# Energetski_dio.net
KiCad netlist of a schematic drawn in Altium Designer
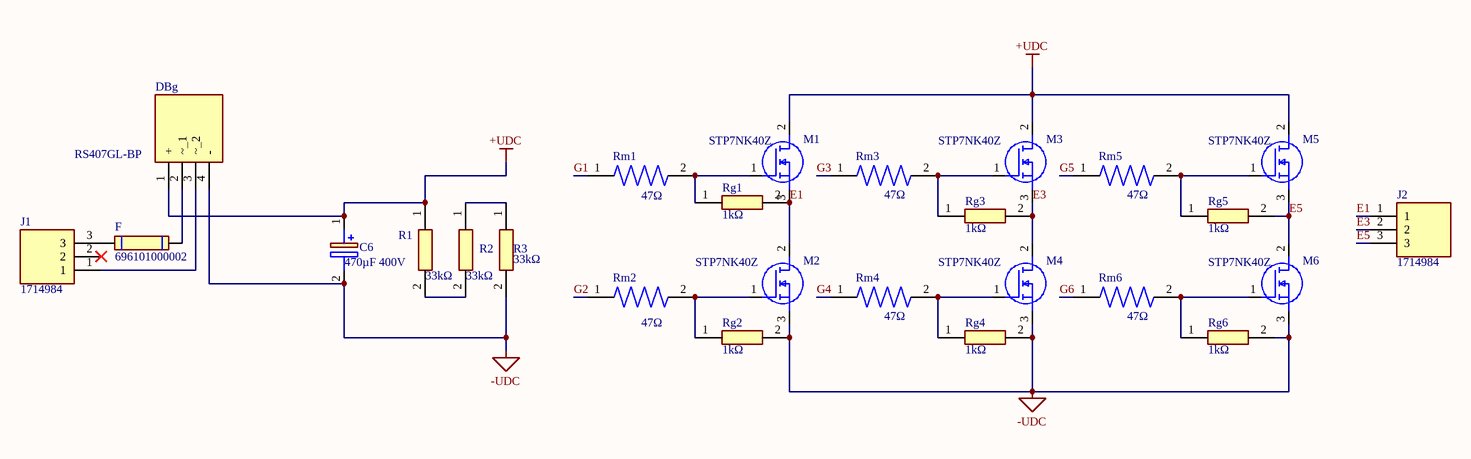
[diagram p0: Energetski_dio.SchDoc]

(export (version "E")
  (design (tool "Eeschema 10.0.6"))
  (components
    (comp (ref "C6")
      (value "470µF 400V")
      (footprint "6")
      (description "Capacitor Polarised")
      (fields
        (field (name "MANUFACTURER_PART_NUMBER") "LLG2G471MELB35")
        (field (name "MOUSER PART NUMBER") "647-LLG2G471MELB35")
      )
      (libsource (lib "Trofazni_invertor_SchLib") (part "LLG2G471MELB35_1"))
    )
    (comp (ref "DBg")
      (value "RS407GL-BP")
      (footprint "10")
      (description "Bridge Rectifier")
      (fields (field (name "MOUSER PART NUMBER") "833-RS407GL-BP"))
      (libsource (lib "Trofazni_invertor_SchLib") (part "RS407GL-BP"))
    )
    (comp (ref "F")
      (value "696101000002")
      (footprint "696101000002")
      (description "Fuse Block 10 A 250V 1 Circuit Cartridge Through Hole")
      (fields (field (name "MF") "Wurth Elektronik"))
      (libsource (lib "Trofazni_invertor_SchLib") (part "696101000002"))
    )
    (comp (ref "J1")
      (value "1714984")
      (footprint "3")
      (description "Connector")
      (fields (field (name "MOUSER PART NUMBER") "651-1714984"))
      (libsource (lib "") (part "1714984_1"))
    )
    (comp (ref "J2")
      (value "1714984")
      (footprint "3")
      (description "Connector")
      (fields (field (name "MOUSER PART NUMBER") "651-1714984"))
      (libsource (lib "Trofazni_invertor_SchLib") (part "1714984"))
    )
    (comp (ref "M1")
      (value "STP7NK40Z")
      (footprint "2")
      (description "MOSFET (N-Channel)")
      (fields
        (field (name "MANUFACTURER_PART_NUMBER") "STP7NK40ZFP")
        (field (name "MOUSER PART NUMBER") "511-STP7NK40ZFP")
      )
      (libsource (lib "Trofazni_invertor_SchLib") (part "STP7NK40ZFP"))
    )
    (comp (ref "M2")
      (value "STP7NK40Z")
      (footprint "2")
      (description "MOSFET (N-Channel)")
      (fields
        (field (name "MANUFACTURER_PART_NUMBER") "STP7NK40ZFP")
        (field (name "MOUSER PART NUMBER") "511-STP7NK40ZFP")
      )
      (libsource (lib "Trofazni_invertor_SchLib") (part "STP7NK40ZFP"))
    )
    (comp (ref "M3")
      (value "STP7NK40Z")
      (footprint "2")
      (description "MOSFET (N-Channel)")
      (fields
        (field (name "MANUFACTURER_PART_NUMBER") "STP7NK40ZFP")
        (field (name "MOUSER PART NUMBER") "511-STP7NK40ZFP")
      )
      (libsource (lib "Trofazni_invertor_SchLib") (part "STP7NK40ZFP"))
    )
    (comp (ref "M4")
      (value "STP7NK40Z")
      (footprint "2")
      (description "MOSFET (N-Channel)")
      (fields
        (field (name "MANUFACTURER_PART_NUMBER") "STP7NK40ZFP")
        (field (name "MOUSER PART NUMBER") "511-STP7NK40ZFP")
      )
      (libsource (lib "Trofazni_invertor_SchLib") (part "STP7NK40ZFP"))
    )
    (comp (ref "M5")
      (value "STP7NK40Z")
      (footprint "2")
      (description "MOSFET (N-Channel)")
      (fields
        (field (name "MANUFACTURER_PART_NUMBER") "STP7NK40ZFP")
        (field (name "MOUSER PART NUMBER") "511-STP7NK40ZFP")
      )
      (libsource (lib "Trofazni_invertor_SchLib") (part "STP7NK40ZFP"))
    )
    (comp (ref "M6")
      (value "STP7NK40Z")
      (footprint "2")
      (description "MOSFET (N-Channel)")
      (fields
        (field (name "MANUFACTURER_PART_NUMBER") "STP7NK40ZFP")
        (field (name "MOUSER PART NUMBER") "511-STP7NK40ZFP")
      )
      (libsource (lib "Trofazni_invertor_SchLib") (part "STP7NK40ZFP"))
    )
    (comp (ref "R1")
      (value "33kΩ")
      (footprint "18")
      (description "Resistor")
      (fields
        (field (name "MANUFACTURER_PART_NUMBER") "CFR-50JB-52-33K")
        (field (name "MOUSER PART NUMBER") "603-CFR-50JB-52-33K")
      )
      (libsource (lib "Trofazni_invertor_SchLib") (part "CFR-50JB-52-33K"))
    )
    (comp (ref "R2")
      (value "33kΩ")
      (footprint "18")
      (description "Resistor")
      (fields
        (field (name "MANUFACTURER_PART_NUMBER") "CFR-50JB-52-33K")
        (field (name "MOUSER PART NUMBER") "603-CFR-50JB-52-33K")
      )
      (libsource (lib "Trofazni_invertor_SchLib") (part "CFR-50JB-52-33K"))
    )
    (comp (ref "R3")
      (value "33kΩ")
      (footprint "18")
      (description "Resistor")
      (fields
        (field (name "MANUFACTURER_PART_NUMBER") "CFR-50JB-52-33K")
        (field (name "MOUSER PART NUMBER") "603-CFR-50JB-52-33K")
      )
      (libsource (lib "Trofazni_invertor_SchLib") (part "CFR-50JB-52-33K"))
    )
    (comp (ref "Rg1")
      (value "1kΩ")
      (footprint "SamacSys:RESAD1590W60L630D240")
      (description "Resistor")
      (fields (field (name "MANUFACTURER_PART_NUMBER") "CFR-25JB-52-1K"))
      (libsource (lib "Trofazni_invertor_SchLib") (part "CFR-25JB-52-1K"))
    )
    (comp (ref "Rg2")
      (value "1kΩ")
      (footprint "SamacSys:RESAD1590W60L630D240")
      (description "Resistor")
      (fields (field (name "MANUFACTURER_PART_NUMBER") "CFR-25JB-52-1K"))
      (libsource (lib "Trofazni_invertor_SchLib") (part "CFR-25JB-52-1K"))
    )
    (comp (ref "Rg3")
      (value "1kΩ")
      (footprint "SamacSys:RESAD1590W60L630D240")
      (description "Resistor")
      (fields (field (name "MANUFACTURER_PART_NUMBER") "CFR-25JB-52-1K"))
      (libsource (lib "Trofazni_invertor_SchLib") (part "CFR-25JB-52-1K"))
    )
    (comp (ref "Rg4")
      (value "1kΩ")
      (footprint "SamacSys:RESAD1590W60L630D240")
      (description "Resistor")
      (fields (field (name "MANUFACTURER_PART_NUMBER") "CFR-25JB-52-1K"))
      (libsource (lib "Trofazni_invertor_SchLib") (part "CFR-25JB-52-1K"))
    )
    (comp (ref "Rg5")
      (value "1kΩ")
      (footprint "SamacSys:RESAD1590W60L630D240")
      (description "Resistor")
      (fields (field (name "MANUFACTURER_PART_NUMBER") "CFR-25JB-52-1K"))
      (libsource (lib "Trofazni_invertor_SchLib") (part "CFR-25JB-52-1K"))
    )
    (comp (ref "Rg6")
      (value "1kΩ")
      (footprint "SamacSys:RESAD1590W60L630D240")
      (description "Resistor")
      (fields (field (name "MANUFACTURER_PART_NUMBER") "CFR-25JB-52-1K"))
      (libsource (lib "Trofazni_invertor_SchLib") (part "CFR-25JB-52-1K"))
    )
    (comp (ref "Rm1")
      (value "47Ω")
      (footprint "17")
      (description "470 Ohms Â±5% 0.25W, 1/4W Through Hole Resistor Axial - Carbon Film")
      (fields (field (name "TOLERANCE") "5%") (field (name "MF") "TE Connectivity"))
      (libsource (lib "Trofazni_invertor_SchLib") (part "2-1623928-5"))
    )
    (comp (ref "Rm2")
      (value "47Ω")
      (footprint "17")
      (description "470 Ohms Â±5% 0.25W, 1/4W Through Hole Resistor Axial - Carbon Film")
      (fields (field (name "TOLERANCE") "5%") (field (name "MF") "TE Connectivity"))
      (libsource (lib "Trofazni_invertor_SchLib") (part "2-1623928-5"))
    )
    (comp (ref "Rm3")
      (value "47Ω")
      (footprint "17")
      (description "470 Ohms Â±5% 0.25W, 1/4W Through Hole Resistor Axial - Carbon Film")
      (fields (field (name "TOLERANCE") "5%") (field (name "MF") "TE Connectivity"))
      (libsource (lib "Trofazni_invertor_SchLib") (part "2-1623928-5"))
    )
    (comp (ref "Rm4")
      (value "47Ω")
      (footprint "17")
      (description "470 Ohms Â±5% 0.25W, 1/4W Through Hole Resistor Axial - Carbon Film")
      (fields (field (name "TOLERANCE") "5%") (field (name "MF") "TE Connectivity"))
      (libsource (lib "Trofazni_invertor_SchLib") (part "2-1623928-5"))
    )
    (comp (ref "Rm5")
      (value "47Ω")
      (footprint "17")
      (description "470 Ohms Â±5% 0.25W, 1/4W Through Hole Resistor Axial - Carbon Film")
      (fields (field (name "TOLERANCE") "5%") (field (name "MF") "TE Connectivity"))
      (libsource (lib "Trofazni_invertor_SchLib") (part "2-1623928-5"))
    )
    (comp (ref "Rm6")
      (value "47Ω")
      (footprint "17")
      (description "470 Ohms Â±5% 0.25W, 1/4W Through Hole Resistor Axial - Carbon Film")
      (fields (field (name "TOLERANCE") "5%") (field (name "MF") "TE Connectivity"))
      (libsource (lib "Trofazni_invertor_SchLib") (part "2-1623928-5"))
    )
  )
  (nets
    (net (code "1") (name "+UDC") (class "Default")
      (node (ref "C6") (pin "1") (pinfunction "+_1") (pintype "passive"))
      (node (ref "DBg") (pin "1") (pinfunction "+_1") (pintype "passive"))
      (node (ref "M1") (pin "2") (pinfunction "D_2") (pintype "passive"))
      (node (ref "M3") (pin "2") (pinfunction "D_2") (pintype "passive"))
      (node (ref "M5") (pin "2") (pinfunction "D_2") (pintype "passive"))
      (node (ref "R1") (pin "1") (pinfunction "1_1") (pintype "passive"))
    )
    (net (code "2") (name "-UDC") (class "Default")
      (node (ref "C6") (pin "2") (pinfunction "-_2") (pintype "passive"))
      (node (ref "DBg") (pin "4") (pinfunction "-_4") (pintype "passive"))
      (node (ref "M2") (pin "3") (pinfunction "S_3") (pintype "passive"))
      (node (ref "M4") (pin "3") (pinfunction "S_3") (pintype "passive"))
      (node (ref "M6") (pin "3") (pinfunction "S_3") (pintype "passive"))
      (node (ref "R3") (pin "2") (pinfunction "2_2") (pintype "passive"))
      (node (ref "Rg2") (pin "2") (pinfunction "2_2") (pintype "passive"))
      (node (ref "Rg4") (pin "2") (pinfunction "2_2") (pintype "passive"))
      (node (ref "Rg6") (pin "2") (pinfunction "2_2") (pintype "passive"))
    )
    (net (code "3") (name "/E1") (class "Default")
      (node (ref "J2") (pin "1") (pinfunction "1_1") (pintype "passive"))
      (node (ref "M1") (pin "3") (pinfunction "S_3") (pintype "passive"))
      (node (ref "M2") (pin "2") (pinfunction "D_2") (pintype "passive"))
      (node (ref "Rg1") (pin "2") (pinfunction "2_2") (pintype "passive"))
    )
    (net (code "4") (name "/E3") (class "Default")
      (node (ref "J2") (pin "2") (pinfunction "2_2") (pintype "passive"))
      (node (ref "M3") (pin "3") (pinfunction "S_3") (pintype "passive"))
      (node (ref "M4") (pin "2") (pinfunction "D_2") (pintype "passive"))
      (node (ref "Rg3") (pin "2") (pinfunction "2_2") (pintype "passive"))
    )
    (net (code "5") (name "/E5") (class "Default")
      (node (ref "J2") (pin "3") (pinfunction "3_3") (pintype "passive"))
      (node (ref "M5") (pin "3") (pinfunction "S_3") (pintype "passive"))
      (node (ref "M6") (pin "2") (pinfunction "D_2") (pintype "passive"))
      (node (ref "Rg5") (pin "2") (pinfunction "2_2") (pintype "passive"))
    )
    (net (code "6") (name "/G1") (class "Default")
      (node (ref "Rm1") (pin "1") (pinfunction "1_1") (pintype "passive"))
    )
    (net (code "7") (name "/G2") (class "Default")
      (node (ref "Rm2") (pin "1") (pinfunction "1_1") (pintype "passive"))
    )
    (net (code "8") (name "/G3") (class "Default")
      (node (ref "Rm3") (pin "1") (pinfunction "1_1") (pintype "passive"))
    )
    (net (code "9") (name "/G4") (class "Default")
      (node (ref "Rm4") (pin "1") (pinfunction "1_1") (pintype "passive"))
    )
    (net (code "10") (name "/G5") (class "Default")
      (node (ref "Rm5") (pin "1") (pinfunction "1_1") (pintype "passive"))
    )
    (net (code "11") (name "/G6") (class "Default")
      (node (ref "Rm6") (pin "1") (pinfunction "1_1") (pintype "passive"))
    )
    (net (code "12") (name "Net-(DBg-~_1)") (class "Default")
      (node (ref "DBg") (pin "2") (pinfunction "~_1_2") (pintype "passive"))
      (node (ref "F") (pin "2") (pinfunction "2_2") (pintype "passive"))
    )
    (net (code "13") (name "Net-(DBg-~_2)") (class "Default")
      (node (ref "DBg") (pin "3") (pinfunction "~_2_3") (pintype "passive"))
      (node (ref "J1") (pin "1") (pinfunction "1_1") (pintype "passive"))
    )
    (net (code "14") (name "Net-(F-Pad1)") (class "Default")
      (node (ref "F") (pin "1") (pinfunction "1_1") (pintype "passive"))
      (node (ref "J1") (pin "3") (pinfunction "3_3") (pintype "passive"))
    )
    (net (code "15") (name "Net-(M1-G)") (class "Default")
      (node (ref "M1") (pin "1") (pinfunction "G_1") (pintype "passive"))
      (node (ref "Rg1") (pin "1") (pinfunction "1_1") (pintype "passive"))
      (node (ref "Rm1") (pin "2") (pinfunction "2_2") (pintype "passive"))
    )
    (net (code "16") (name "Net-(M2-G)") (class "Default")
      (node (ref "M2") (pin "1") (pinfunction "G_1") (pintype "passive"))
      (node (ref "Rg2") (pin "1") (pinfunction "1_1") (pintype "passive"))
      (node (ref "Rm2") (pin "2") (pinfunction "2_2") (pintype "passive"))
    )
    (net (code "17") (name "Net-(M3-G)") (class "Default")
      (node (ref "M3") (pin "1") (pinfunction "G_1") (pintype "passive"))
      (node (ref "Rg3") (pin "1") (pinfunction "1_1") (pintype "passive"))
      (node (ref "Rm3") (pin "2") (pinfunction "2_2") (pintype "passive"))
    )
    (net (code "18") (name "Net-(M4-G)") (class "Default")
      (node (ref "M4") (pin "1") (pinfunction "G_1") (pintype "passive"))
      (node (ref "Rg4") (pin "1") (pinfunction "1_1") (pintype "passive"))
      (node (ref "Rm4") (pin "2") (pinfunction "2_2") (pintype "passive"))
    )
    (net (code "19") (name "Net-(M5-G)") (class "Default")
      (node (ref "M5") (pin "1") (pinfunction "G_1") (pintype "passive"))
      (node (ref "Rg5") (pin "1") (pinfunction "1_1") (pintype "passive"))
      (node (ref "Rm5") (pin "2") (pinfunction "2_2") (pintype "passive"))
    )
    (net (code "20") (name "Net-(M6-G)") (class "Default")
      (node (ref "M6") (pin "1") (pinfunction "G_1") (pintype "passive"))
      (node (ref "Rg6") (pin "1") (pinfunction "1_1") (pintype "passive"))
      (node (ref "Rm6") (pin "2") (pinfunction "2_2") (pintype "passive"))
    )
    (net (code "21") (name "Net-(R1-Pad2)") (class "Default")
      (node (ref "R1") (pin "2") (pinfunction "2_2") (pintype "passive"))
      (node (ref "R2") (pin "2") (pinfunction "2_2") (pintype "passive"))
    )
    (net (code "22") (name "Net-(R2-Pad1)") (class "Default")
      (node (ref "R2") (pin "1") (pinfunction "1_1") (pintype "passive"))
      (node (ref "R3") (pin "1") (pinfunction "1_1") (pintype "passive"))
    )
    (net (code "23") (name "unconnected-(J1-Pad2)") (class "Default")
      (node (ref "J1") (pin "2") (pinfunction "2_2") (pintype "passive+no_connect"))
    )
  )
)
